# BLDC-Controller-Open-Source.net
KiCad netlist of a schematic drawn in EAGLE
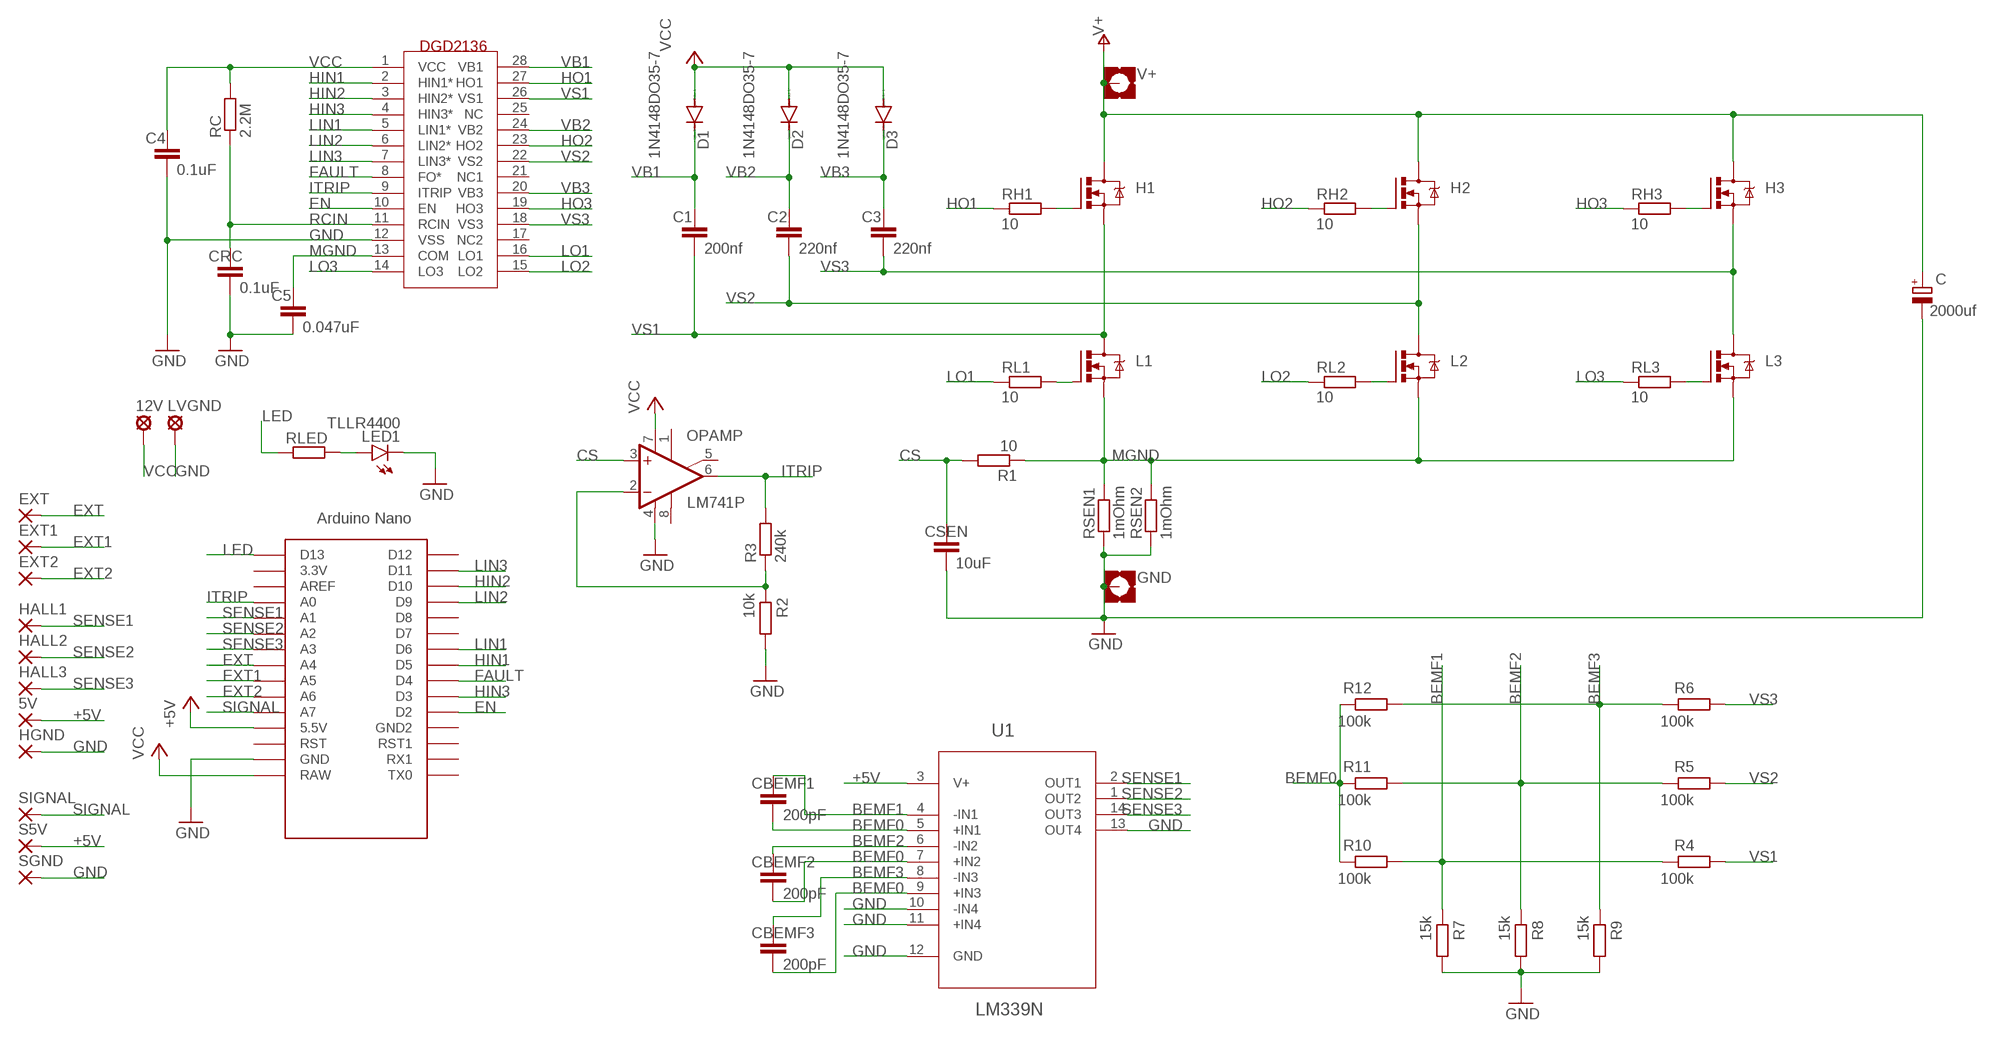
[diagram p0: schematic, sheet 1]

(export (version "E")
  (design (tool "Eeschema 10.0.6"))
  (components
    (comp (ref "5V")
      (value "1,6/0,9")
      (footprint "eagle-import:1,6_0,9")
      (libsource (lib "eagle-import") (part "1,6/0,9"))
    )
    (comp (ref "12V")
      (value "MCS10B")
      (footprint "eagle-import:MCS10B")
      (libsource (lib "eagle-import") (part "MCS10B"))
    )
    (comp (ref "C")
      (value "2000uf")
      (footprint "eagle-import:E7,5-16")
      (libsource (lib "eagle-import") (part "CPOL-EUE7.5-16"))
    )
    (comp (ref "C1")
      (value "200nf")
      (footprint "eagle-import:C025-025X050")
      (libsource (lib "eagle-import") (part "C-EU025-025X050"))
    )
    (comp (ref "C2")
      (value "220nf")
      (footprint "eagle-import:C025-025X050")
      (libsource (lib "eagle-import") (part "C-EU025-025X050"))
    )
    (comp (ref "C3")
      (value "220nf")
      (footprint "eagle-import:C025-025X050")
      (libsource (lib "eagle-import") (part "C-EU025-025X050"))
    )
    (comp (ref "C4")
      (value "0.1uF")
      (footprint "eagle-import:C025-025X050")
      (libsource (lib "eagle-import") (part "C-EU025-025X050"))
    )
    (comp (ref "C5")
      (value "0.047uF")
      (footprint "eagle-import:C025-025X050")
      (libsource (lib "eagle-import") (part "C-EU025-025X050"))
    )
    (comp (ref "CBEMF1")
      (value "200pF")
      (footprint "eagle-import:C025-025X050")
      (libsource (lib "eagle-import") (part "C-EU025-025X050"))
    )
    (comp (ref "CBEMF2")
      (value "200pF")
      (footprint "eagle-import:C025-025X050")
      (libsource (lib "eagle-import") (part "C-EU025-025X050"))
    )
    (comp (ref "CBEMF3")
      (value "200pF")
      (footprint "eagle-import:C025-025X050")
      (libsource (lib "eagle-import") (part "C-EU025-025X050"))
    )
    (comp (ref "CRC")
      (value "0.1uF")
      (footprint "eagle-import:C025-025X050")
      (libsource (lib "eagle-import") (part "C-EU025-025X050"))
    )
    (comp (ref "CSEN")
      (value "10uF")
      (footprint "eagle-import:C025-025X050")
      (libsource (lib "eagle-import") (part "C-EU025-025X050"))
    )
    (comp (ref "D1")
      (value "1N4148DO35-7")
      (footprint "eagle-import:DO35-7")
      (libsource (lib "eagle-import") (part "1N4148DO35-7"))
    )
    (comp (ref "D2")
      (value "1N4148DO35-7")
      (footprint "eagle-import:DO35-7")
      (libsource (lib "eagle-import") (part "1N4148DO35-7"))
    )
    (comp (ref "D3")
      (value "1N4148DO35-7")
      (footprint "eagle-import:DO35-7")
      (libsource (lib "eagle-import") (part "1N4148DO35-7"))
    )
    (comp (ref "EXT")
      (value "1,6/0,9")
      (footprint "eagle-import:1,6_0,9")
      (libsource (lib "eagle-import") (part "1,6/0,9"))
    )
    (comp (ref "EXT1")
      (value "1,6/0,9")
      (footprint "eagle-import:1,6_0,9")
      (libsource (lib "eagle-import") (part "1,6/0,9"))
    )
    (comp (ref "EXT2")
      (value "1,6/0,9")
      (footprint "eagle-import:1,6_0,9")
      (libsource (lib "eagle-import") (part "1,6/0,9"))
    )
    (comp (ref "GND")
      (value "MOUNT-PAD-SQUARE3.6")
      (footprint "eagle-import:3,6-PAD-SQUARE")
      (libsource (lib "eagle-import") (part "MOUNT-PAD-SQUARE3.6"))
    )
    (comp (ref "H1")
      (value "IRF540")
      (footprint "eagle-import:TO220BV")
      (libsource (lib "eagle-import") (part "IRF540"))
    )
    (comp (ref "H2")
      (value "IRF540")
      (footprint "eagle-import:TO220BV")
      (libsource (lib "eagle-import") (part "IRF540"))
    )
    (comp (ref "H3")
      (value "IRF540")
      (footprint "eagle-import:TO220BV")
      (libsource (lib "eagle-import") (part "IRF540"))
    )
    (comp (ref "HALL1")
      (value "1,6/0,9")
      (footprint "eagle-import:1,6_0,9")
      (libsource (lib "eagle-import") (part "1,6/0,9"))
    )
    (comp (ref "HALL2")
      (value "1,6/0,9")
      (footprint "eagle-import:1,6_0,9")
      (libsource (lib "eagle-import") (part "1,6/0,9"))
    )
    (comp (ref "HALL3")
      (value "1,6/0,9")
      (footprint "eagle-import:1,6_0,9")
      (libsource (lib "eagle-import") (part "1,6/0,9"))
    )
    (comp (ref "HGND")
      (value "1,6/0,9")
      (footprint "eagle-import:1,6_0,9")
      (libsource (lib "eagle-import") (part "1,6/0,9"))
    )
    (comp (ref "L1")
      (value "IRF540")
      (footprint "eagle-import:TO220BV")
      (libsource (lib "eagle-import") (part "IRF540"))
    )
    (comp (ref "L2")
      (value "IRF540")
      (footprint "eagle-import:TO220BV")
      (libsource (lib "eagle-import") (part "IRF540"))
    )
    (comp (ref "L3")
      (value "IRF540")
      (footprint "eagle-import:TO220BV")
      (libsource (lib "eagle-import") (part "IRF540"))
    )
    (comp (ref "LED1")
      (value "TLLR4400")
      (footprint "eagle-import:LED3MM")
      (fields (field (name "MF") "VISHAY SEMICONDUCTOR"))
      (libsource (lib "eagle-import") (part "TLLR4400"))
    )
    (comp (ref "LVGND")
      (value "MCS10B")
      (footprint "eagle-import:MCS10B")
      (libsource (lib "eagle-import") (part "MCS10B"))
    )
    (comp (ref "OPAMP")
      (value "LM741P")
      (footprint "eagle-import:DIL08")
      (libsource (lib "eagle-import") (part "741PLM"))
    )
    (comp (ref "R1")
      (value "10")
      (footprint "eagle-import:0204_7")
      (libsource (lib "eagle-import") (part "rcl_334_R-EU_0204/7"))
    )
    (comp (ref "R2")
      (value "10k")
      (footprint "eagle-import:0204_7")
      (libsource (lib "eagle-import") (part "rcl_334_R-EU_0204/7"))
    )
    (comp (ref "R3")
      (value "240k")
      (footprint "eagle-import:0204_7")
      (libsource (lib "eagle-import") (part "rcl_334_R-EU_0204/7"))
    )
    (comp (ref "R4")
      (value "100k")
      (footprint "eagle-import:0204_7")
      (libsource (lib "eagle-import") (part "rcl_334_R-EU_0204/7"))
    )
    (comp (ref "R5")
      (value "100k")
      (footprint "eagle-import:0204_7")
      (libsource (lib "eagle-import") (part "rcl_334_R-EU_0204/7"))
    )
    (comp (ref "R6")
      (value "100k")
      (footprint "eagle-import:0204_7")
      (libsource (lib "eagle-import") (part "rcl_334_R-EU_0204/7"))
    )
    (comp (ref "R7")
      (value "15k")
      (footprint "eagle-import:0204_7")
      (libsource (lib "eagle-import") (part "rcl_334_R-EU_0204/7"))
    )
    (comp (ref "R8")
      (value "15k")
      (footprint "eagle-import:0204_7")
      (libsource (lib "eagle-import") (part "rcl_334_R-EU_0204/7"))
    )
    (comp (ref "R9")
      (value "15k")
      (footprint "eagle-import:0204_7")
      (libsource (lib "eagle-import") (part "rcl_334_R-EU_0204/7"))
    )
    (comp (ref "R10")
      (value "100k")
      (footprint "eagle-import:0204_7")
      (libsource (lib "eagle-import") (part "rcl_334_R-EU_0204/7"))
    )
    (comp (ref "R11")
      (value "100k")
      (footprint "eagle-import:0204_7")
      (libsource (lib "eagle-import") (part "rcl_334_R-EU_0204/7"))
    )
    (comp (ref "R12")
      (value "100k")
      (footprint "eagle-import:0204_7")
      (libsource (lib "eagle-import") (part "rcl_334_R-EU_0204/7"))
    )
    (comp (ref "RC")
      (value "2.2M")
      (footprint "eagle-import:0204_7")
      (libsource (lib "eagle-import") (part "rcl_334_R-EU_0204/7"))
    )
    (comp (ref "RH1")
      (value "10")
      (footprint "eagle-import:0204_7")
      (libsource (lib "eagle-import") (part "rcl_334_R-EU_0204/7"))
    )
    (comp (ref "RH2")
      (value "10")
      (footprint "eagle-import:0204_7")
      (libsource (lib "eagle-import") (part "rcl_334_R-EU_0204/7"))
    )
    (comp (ref "RH3")
      (value "10")
      (footprint "eagle-import:0204_7")
      (libsource (lib "eagle-import") (part "rcl_334_R-EU_0204/7"))
    )
    (comp (ref "RL1")
      (value "10")
      (footprint "eagle-import:0204_7")
      (libsource (lib "eagle-import") (part "rcl_334_R-EU_0204/7"))
    )
    (comp (ref "RL2")
      (value "10")
      (footprint "eagle-import:0204_7")
      (libsource (lib "eagle-import") (part "rcl_334_R-EU_0204/7"))
    )
    (comp (ref "RL3")
      (value "10")
      (footprint "eagle-import:0204_7")
      (libsource (lib "eagle-import") (part "rcl_334_R-EU_0204/7"))
    )
    (comp (ref "RLED")
      (value "R-EU_0204/7")
      (footprint "eagle-import:0204_7")
      (libsource (lib "eagle-import") (part "rcl_334_R-EU_0204/7"))
    )
    (comp (ref "RSEN1")
      (value "1mOhm")
      (footprint "eagle-import:R2512")
      (libsource (lib "eagle-import") (part "R-EU_R2512"))
    )
    (comp (ref "RSEN2")
      (value "1mOhm")
      (footprint "eagle-import:R2512")
      (libsource (lib "eagle-import") (part "R-EU_R2512"))
    )
    (comp (ref "S5V")
      (value "1,6/0,9")
      (footprint "eagle-import:1,6_0,9")
      (libsource (lib "eagle-import") (part "1,6/0,9"))
    )
    (comp (ref "SGND")
      (value "1,6/0,9")
      (footprint "eagle-import:1,6_0,9")
      (libsource (lib "eagle-import") (part "1,6/0,9"))
    )
    (comp (ref "SIGNAL")
      (value "1,6/0,9")
      (footprint "eagle-import:1,6_0,9")
      (libsource (lib "eagle-import") (part "1,6/0,9"))
    )
    (comp (ref "U$1")
      (value "NANO")
      (footprint "eagle-import:NANO")
      (libsource (lib "eagle-import") (part "NANO"))
    )
    (comp (ref "U$2")
      (value "DGD2136")
      (footprint "eagle-import:DGD2136")
      (libsource (lib "eagle-import") (part "DGD2136"))
    )
    (comp (ref "U1")
      (value "LM339N")
      (footprint "eagle-import:DIP254P762X508-14")
      (fields (field (name "MF") "ON Semiconductor"))
      (libsource (lib "eagle-import") (part "LM339N"))
    )
    (comp (ref "V+")
      (value "MOUNT-PAD-SQUARE3.6")
      (footprint "eagle-import:3,6-PAD-SQUARE")
      (libsource (lib "eagle-import") (part "MOUNT-PAD-SQUARE3.6"))
    )
  )
  (nets
    (net (code "1") (name "+5V") (class "Default")
      (node (ref "5V") (pin "1") (pinfunction "P_1") (pintype "passive"))
      (node (ref "S5V") (pin "1") (pinfunction "P_1") (pintype "passive"))
      (node (ref "U$1") (pin "5V") (pinfunction "5.5V_5V") (pintype "bidirectional"))
      (node (ref "U1") (pin "3") (pinfunction "V+_3") (pintype "power_in"))
    )
    (net (code "2") (name "/BEMF0") (class "Default")
      (node (ref "CBEMF1") (pin "2") (pinfunction "2_2") (pintype "passive"))
      (node (ref "CBEMF2") (pin "2") (pinfunction "2_2") (pintype "passive"))
      (node (ref "CBEMF3") (pin "2") (pinfunction "2_2") (pintype "passive"))
      (node (ref "R10") (pin "2") (pinfunction "2_2") (pintype "passive"))
      (node (ref "R11") (pin "2") (pinfunction "2_2") (pintype "passive"))
      (node (ref "R12") (pin "2") (pinfunction "2_2") (pintype "passive"))
      (node (ref "U1") (pin "5") (pinfunction "+IN1_5") (pintype "input"))
      (node (ref "U1") (pin "7") (pinfunction "+IN2_7") (pintype "input"))
      (node (ref "U1") (pin "9") (pinfunction "+IN3_9") (pintype "input"))
    )
    (net (code "3") (name "/BEMF1") (class "Default")
      (node (ref "CBEMF1") (pin "1") (pinfunction "1_1") (pintype "passive"))
      (node (ref "R10") (pin "1") (pinfunction "1_1") (pintype "passive"))
      (node (ref "R4") (pin "2") (pinfunction "2_2") (pintype "passive"))
      (node (ref "R7") (pin "2") (pinfunction "2_2") (pintype "passive"))
      (node (ref "U1") (pin "4") (pinfunction "-IN1_4") (pintype "input"))
    )
    (net (code "4") (name "/BEMF2") (class "Default")
      (node (ref "CBEMF2") (pin "1") (pinfunction "1_1") (pintype "passive"))
      (node (ref "R11") (pin "1") (pinfunction "1_1") (pintype "passive"))
      (node (ref "R5") (pin "2") (pinfunction "2_2") (pintype "passive"))
      (node (ref "R8") (pin "2") (pinfunction "2_2") (pintype "passive"))
      (node (ref "U1") (pin "6") (pinfunction "-IN2_6") (pintype "input"))
    )
    (net (code "5") (name "/BEMF3") (class "Default")
      (node (ref "CBEMF3") (pin "1") (pinfunction "1_1") (pintype "passive"))
      (node (ref "R12") (pin "1") (pinfunction "1_1") (pintype "passive"))
      (node (ref "R6") (pin "2") (pinfunction "2_2") (pintype "passive"))
      (node (ref "R9") (pin "2") (pinfunction "2_2") (pintype "passive"))
      (node (ref "U1") (pin "8") (pinfunction "-IN3_8") (pintype "input"))
    )
    (net (code "6") (name "/CS") (class "Default")
      (node (ref "CSEN") (pin "1") (pinfunction "1_1") (pintype "passive"))
      (node (ref "OPAMP") (pin "3") (pinfunction "+IN_3") (pintype "input"))
      (node (ref "R1") (pin "2") (pinfunction "2_2") (pintype "passive"))
    )
    (net (code "7") (name "/EN") (class "Default")
      (node (ref "U$1") (pin "D2") (pinfunction "D2_D2") (pintype "bidirectional"))
      (node (ref "U$2") (pin "10") (pinfunction "EN_10") (pintype "bidirectional"))
    )
    (net (code "8") (name "/EXT") (class "Default")
      (node (ref "EXT") (pin "1") (pinfunction "P_1") (pintype "passive"))
      (node (ref "U$1") (pin "A4") (pinfunction "A4_A4") (pintype "bidirectional"))
    )
    (net (code "9") (name "/EXT1") (class "Default")
      (node (ref "EXT1") (pin "1") (pinfunction "P_1") (pintype "passive"))
      (node (ref "U$1") (pin "A5") (pinfunction "A5_A5") (pintype "bidirectional"))
    )
    (net (code "10") (name "/EXT2") (class "Default")
      (node (ref "EXT2") (pin "1") (pinfunction "P_1") (pintype "passive"))
      (node (ref "U$1") (pin "A6") (pinfunction "A6_A6") (pintype "bidirectional"))
    )
    (net (code "11") (name "/FAULT") (class "Default")
      (node (ref "U$1") (pin "D4") (pinfunction "D4_D4") (pintype "bidirectional"))
      (node (ref "U$2") (pin "8") (pinfunction "FO*_8") (pintype "bidirectional"))
    )
    (net (code "12") (name "/HIN1") (class "Default")
      (node (ref "U$1") (pin "D5") (pinfunction "D5_D5") (pintype "bidirectional"))
      (node (ref "U$2") (pin "2") (pinfunction "HIN1*_2") (pintype "bidirectional"))
    )
    (net (code "13") (name "/HIN2") (class "Default")
      (node (ref "U$1") (pin "D10") (pinfunction "D10_D10") (pintype "bidirectional"))
      (node (ref "U$2") (pin "3") (pinfunction "HIN2*_3") (pintype "bidirectional"))
    )
    (net (code "14") (name "/HIN3") (class "Default")
      (node (ref "U$1") (pin "D3") (pinfunction "D3_D3") (pintype "bidirectional"))
      (node (ref "U$2") (pin "4") (pinfunction "HIN3*_4") (pintype "bidirectional"))
    )
    (net (code "15") (name "/HO1") (class "Default")
      (node (ref "RH1") (pin "1") (pinfunction "1_1") (pintype "passive"))
      (node (ref "U$2") (pin "27") (pinfunction "HO1_27") (pintype "bidirectional"))
    )
    (net (code "16") (name "/HO2") (class "Default")
      (node (ref "RH2") (pin "1") (pinfunction "1_1") (pintype "passive"))
      (node (ref "U$2") (pin "23") (pinfunction "HO2_23") (pintype "bidirectional"))
    )
    (net (code "17") (name "/HO3") (class "Default")
      (node (ref "RH3") (pin "1") (pinfunction "1_1") (pintype "passive"))
      (node (ref "U$2") (pin "19") (pinfunction "HO3_19") (pintype "bidirectional"))
    )
    (net (code "18") (name "/ITRIP") (class "Default")
      (node (ref "OPAMP") (pin "6") (pinfunction "OUT_6") (pintype "output"))
      (node (ref "R3") (pin "2") (pinfunction "2_2") (pintype "passive"))
      (node (ref "U$1") (pin "A0") (pinfunction "A0_A0") (pintype "bidirectional"))
      (node (ref "U$2") (pin "9") (pinfunction "ITRIP_9") (pintype "bidirectional"))
    )
    (net (code "19") (name "/LED") (class "Default")
      (node (ref "RLED") (pin "1") (pinfunction "1_1") (pintype "passive"))
      (node (ref "U$1") (pin "D13") (pinfunction "D13_D13") (pintype "bidirectional"))
    )
    (net (code "20") (name "/LIN1") (class "Default")
      (node (ref "U$1") (pin "D6") (pinfunction "D6_D6") (pintype "bidirectional"))
      (node (ref "U$2") (pin "5") (pinfunction "LIN1*_5") (pintype "bidirectional"))
    )
    (net (code "21") (name "/LIN2") (class "Default")
      (node (ref "U$1") (pin "D9") (pinfunction "D9_D9") (pintype "bidirectional"))
      (node (ref "U$2") (pin "6") (pinfunction "LIN2*_6") (pintype "bidirectional"))
    )
    (net (code "22") (name "/LIN3") (class "Default")
      (node (ref "U$1") (pin "D11") (pinfunction "D11_D11") (pintype "bidirectional"))
      (node (ref "U$2") (pin "7") (pinfunction "LIN3*_7") (pintype "bidirectional"))
    )
    (net (code "23") (name "/LO1") (class "Default")
      (node (ref "RL1") (pin "1") (pinfunction "1_1") (pintype "passive"))
      (node (ref "U$2") (pin "16") (pinfunction "LO1_16") (pintype "bidirectional"))
    )
    (net (code "24") (name "/LO2") (class "Default")
      (node (ref "RL2") (pin "1") (pinfunction "1_1") (pintype "passive"))
      (node (ref "U$2") (pin "15") (pinfunction "LO2_15") (pintype "bidirectional"))
    )
    (net (code "25") (name "/LO3") (class "Default")
      (node (ref "RL3") (pin "1") (pinfunction "1_1") (pintype "passive"))
      (node (ref "U$2") (pin "14") (pinfunction "LO3_14") (pintype "bidirectional"))
    )
    (net (code "26") (name "/MGND") (class "Default")
      (node (ref "C5") (pin "1") (pinfunction "1_1") (pintype "passive"))
      (node (ref "L1") (pin "S") (pinfunction "S_S") (pintype "passive"))
      (node (ref "L2") (pin "S") (pinfunction "S_S") (pintype "passive"))
      (node (ref "L3") (pin "S") (pinfunction "S_S") (pintype "passive"))
      (node (ref "R1") (pin "1") (pinfunction "1_1") (pintype "passive"))
      (node (ref "RSEN1") (pin "2") (pinfunction "2_2") (pintype "passive"))
      (node (ref "RSEN2") (pin "2") (pinfunction "2_2") (pintype "passive"))
      (node (ref "U$2") (pin "13") (pinfunction "COM_13") (pintype "bidirectional"))
    )
    (net (code "27") (name "/RCIN") (class "Default")
      (node (ref "CRC") (pin "1") (pinfunction "1_1") (pintype "passive"))
      (node (ref "RC") (pin "1") (pinfunction "1_1") (pintype "passive"))
      (node (ref "U$2") (pin "11") (pinfunction "RCIN_11") (pintype "bidirectional"))
    )
    (net (code "28") (name "/SENSE1") (class "Default")
      (node (ref "HALL1") (pin "1") (pinfunction "P_1") (pintype "passive"))
      (node (ref "U$1") (pin "A1") (pinfunction "A1_A1") (pintype "bidirectional"))
      (node (ref "U1") (pin "2") (pinfunction "OUT1_2") (pintype "output"))
    )
    (net (code "29") (name "/SENSE2") (class "Default")
      (node (ref "HALL2") (pin "1") (pinfunction "P_1") (pintype "passive"))
      (node (ref "U$1") (pin "A2") (pinfunction "A2_A2") (pintype "bidirectional"))
      (node (ref "U1") (pin "1") (pinfunction "OUT2_1") (pintype "output"))
    )
    (net (code "30") (name "/SENSE3") (class "Default")
      (node (ref "HALL3") (pin "1") (pinfunction "P_1") (pintype "passive"))
      (node (ref "U$1") (pin "A3") (pinfunction "A3_A3") (pintype "bidirectional"))
      (node (ref "U1") (pin "14") (pinfunction "OUT3_14") (pintype "output"))
    )
    (net (code "31") (name "/SIGNAL") (class "Default")
      (node (ref "SIGNAL") (pin "1") (pinfunction "P_1") (pintype "passive"))
      (node (ref "U$1") (pin "A7") (pinfunction "A7_A7") (pintype "bidirectional"))
    )
    (net (code "32") (name "/VB1") (class "Default")
      (node (ref "C1") (pin "1") (pinfunction "1_1") (pintype "passive"))
      (node (ref "D1") (pin "C") (pinfunction "C_C") (pintype "passive"))
      (node (ref "U$2") (pin "28") (pinfunction "VB1_28") (pintype "bidirectional"))
    )
    (net (code "33") (name "/VB2") (class "Default")
      (node (ref "C2") (pin "1") (pinfunction "1_1") (pintype "passive"))
      (node (ref "D2") (pin "C") (pinfunction "C_C") (pintype "passive"))
      (node (ref "U$2") (pin "24") (pinfunction "VB2_24") (pintype "bidirectional"))
    )
    (net (code "34") (name "/VB3") (class "Default")
      (node (ref "C3") (pin "1") (pinfunction "1_1") (pintype "passive"))
      (node (ref "D3") (pin "C") (pinfunction "C_C") (pintype "passive"))
      (node (ref "U$2") (pin "20") (pinfunction "VB3_20") (pintype "bidirectional"))
    )
    (net (code "35") (name "/VS1") (class "Default")
      (node (ref "C1") (pin "2") (pinfunction "2_2") (pintype "passive"))
      (node (ref "H1") (pin "S") (pinfunction "S_S") (pintype "passive"))
      (node (ref "L1") (pin "D") (pinfunction "D_D") (pintype "passive"))
      (node (ref "R4") (pin "1") (pinfunction "1_1") (pintype "passive"))
      (node (ref "U$2") (pin "26") (pinfunction "VS1_26") (pintype "bidirectional"))
    )
    (net (code "36") (name "/VS2") (class "Default")
      (node (ref "C2") (pin "2") (pinfunction "2_2") (pintype "passive"))
      (node (ref "H2") (pin "S") (pinfunction "S_S") (pintype "passive"))
      (node (ref "L2") (pin "D") (pinfunction "D_D") (pintype "passive"))
      (node (ref "R5") (pin "1") (pinfunction "1_1") (pintype "passive"))
      (node (ref "U$2") (pin "22") (pinfunction "VS2_22") (pintype "bidirectional"))
    )
    (net (code "37") (name "/VS3") (class "Default")
      (node (ref "C3") (pin "2") (pinfunction "2_2") (pintype "passive"))
      (node (ref "H3") (pin "S") (pinfunction "S_S") (pintype "passive"))
      (node (ref "L3") (pin "D") (pinfunction "D_D") (pintype "passive"))
      (node (ref "R6") (pin "1") (pinfunction "1_1") (pintype "passive"))
      (node (ref "U$2") (pin "18") (pinfunction "VS3_18") (pintype "bidirectional"))
    )
    (net (code "38") (name "GND") (class "Default")
      (node (ref "C") (pin "-") (pinfunction "-_-") (pintype "passive"))
      (node (ref "C4") (pin "2") (pinfunction "2_2") (pintype "passive"))
      (node (ref "C5") (pin "2") (pinfunction "2_2") (pintype "passive"))
      (node (ref "CRC") (pin "2") (pinfunction "2_2") (pintype "passive"))
      (node (ref "CSEN") (pin "2") (pinfunction "2_2") (pintype "passive"))
      (node (ref "GND") (pin "B3,6") (pinfunction "MOUNT_B3,6") (pintype "passive"))
      (node (ref "HGND") (pin "1") (pinfunction "P_1") (pintype "passive"))
      (node (ref "LED1") (pin "K") (pinfunction "C_K") (pintype "passive"))
      (node (ref "LVGND") (pin "MP") (pinfunction "MP_MP") (pintype "passive"))
      (node (ref "OPAMP") (pin "4") (pinfunction "V-_4") (pintype "power_in"))
      (node (ref "R2") (pin "1") (pinfunction "1_1") (pintype "passive"))
      (node (ref "R7") (pin "1") (pinfunction "1_1") (pintype "passive"))
      (node (ref "R8") (pin "1") (pinfunction "1_1") (pintype "passive"))
      (node (ref "R9") (pin "1") (pinfunction "1_1") (pintype "passive"))
      (node (ref "RSEN1") (pin "1") (pinfunction "1_1") (pintype "passive"))
      (node (ref "RSEN2") (pin "1") (pinfunction "1_1") (pintype "passive"))
      (node (ref "SGND") (pin "1") (pinfunction "P_1") (pintype "passive"))
      (node (ref "U$1") (pin "GND") (pinfunction "GND_GND") (pintype "bidirectional"))
      (node (ref "U$2") (pin "12") (pinfunction "VSS_12") (pintype "bidirectional"))
      (node (ref "U1") (pin "10") (pinfunction "-IN4_10") (pintype "input"))
      (node (ref "U1") (pin "11") (pinfunction "+IN4_11") (pintype "input"))
      (node (ref "U1") (pin "12") (pinfunction "GND_12") (pintype "passive"))
      (node (ref "U1") (pin "13") (pinfunction "OUT4_13") (pintype "output"))
    )
    (net (code "39") (name "Net-(H1-PadG)") (class "Default")
      (node (ref "H1") (pin "G") (pinfunction "G_G") (pintype "passive"))
      (node (ref "RH1") (pin "2") (pinfunction "2_2") (pintype "passive"))
    )
    (net (code "40") (name "Net-(H2-PadG)") (class "Default")
      (node (ref "H2") (pin "G") (pinfunction "G_G") (pintype "passive"))
      (node (ref "RH2") (pin "2") (pinfunction "2_2") (pintype "passive"))
    )
    (net (code "41") (name "Net-(H3-PadG)") (class "Default")
      (node (ref "H3") (pin "G") (pinfunction "G_G") (pintype "passive"))
      (node (ref "RH3") (pin "2") (pinfunction "2_2") (pintype "passive"))
    )
    (net (code "42") (name "Net-(L1-PadG)") (class "Default")
      (node (ref "L1") (pin "G") (pinfunction "G_G") (pintype "passive"))
      (node (ref "RL1") (pin "2") (pinfunction "2_2") (pintype "passive"))
    )
    (net (code "43") (name "Net-(L2-PadG)") (class "Default")
      (node (ref "L2") (pin "G") (pinfunction "G_G") (pintype "passive"))
      (node (ref "RL2") (pin "2") (pinfunction "2_2") (pintype "passive"))
    )
    (net (code "44") (name "Net-(L3-PadG)") (class "Default")
      (node (ref "L3") (pin "G") (pinfunction "G_G") (pintype "passive"))
      (node (ref "RL3") (pin "2") (pinfunction "2_2") (pintype "passive"))
    )
    (net (code "45") (name "Net-(LED1-PadA)") (class "Default")
      (node (ref "LED1") (pin "A") (pinfunction "A_A") (pintype "passive"))
      (node (ref "RLED") (pin "2") (pinfunction "2_2") (pintype "passive"))
    )
    (net (code "46") (name "Net-(OPAMP--IN)") (class "Default")
      (node (ref "OPAMP") (pin "2") (pinfunction "-IN_2") (pintype "input"))
      (node (ref "R2") (pin "2") (pinfunction "2_2") (pintype "passive"))
      (node (ref "R3") (pin "1") (pinfunction "1_1") (pintype "passive"))
    )
    (net (code "47") (name "V+") (class "Default")
      (node (ref "C") (pin "+") (pinfunction "+_+") (pintype "passive"))
      (node (ref "H1") (pin "D") (pinfunction "D_D") (pintype "passive"))
      (node (ref "H2") (pin "D") (pinfunction "D_D") (pintype "passive"))
      (node (ref "H3") (pin "D") (pinfunction "D_D") (pintype "passive"))
      (node (ref "V+") (pin "B3,6") (pinfunction "MOUNT_B3,6") (pintype "passive"))
    )
    (net (code "48") (name "VCC") (class "Default")
      (node (ref "12V") (pin "MP") (pinfunction "MP_MP") (pintype "passive"))
      (node (ref "C4") (pin "1") (pinfunction "1_1") (pintype "passive"))
      (node (ref "D1") (pin "A") (pinfunction "A_A") (pintype "passive"))
      (node (ref "D2") (pin "A") (pinfunction "A_A") (pintype "passive"))
      (node (ref "D3") (pin "A") (pinfunction "A_A") (pintype "passive"))
      (node (ref "OPAMP") (pin "7") (pinfunction "V+_7") (pintype "power_in"))
      (node (ref "RC") (pin "2") (pinfunction "2_2") (pintype "passive"))
      (node (ref "U$1") (pin "RAW") (pinfunction "RAW_RAW") (pintype "bidirectional"))
      (node (ref "U$2") (pin "1") (pinfunction "VCC_1") (pintype "bidirectional"))
    )
    (net (code "49") (name "unconnected-(OPAMP-ON1-Pad1)") (class "Default")
      (node (ref "OPAMP") (pin "1") (pinfunction "ON1_1") (pintype "passive"))
    )
    (net (code "50") (name "unconnected-(OPAMP-ON2-Pad5)") (class "Default")
      (node (ref "OPAMP") (pin "5") (pinfunction "ON2_5") (pintype "passive"))
    )
    (net (code "51") (name "unconnected-(OPAMP-OPT-Pad8)") (class "Default")
      (node (ref "OPAMP") (pin "8") (pinfunction "OPT_8") (pintype "passive"))
    )
    (net (code "52") (name "unconnected-(U$1-GND2-PadGND1)") (class "Default")
      (node (ref "U$1") (pin "GND1") (pinfunction "GND2_GND1") (pintype "bidirectional"))
    )
    (net (code "53") (name "unconnected-(U$1-Pad3.3V)") (class "Default")
      (node (ref "U$1") (pin "3.3V") (pinfunction "3.3V_3.3V") (pintype "bidirectional"))
    )
    (net (code "54") (name "unconnected-(U$1-PadAREF)") (class "Default")
      (node (ref "U$1") (pin "AREF") (pinfunction "AREF_AREF") (pintype "bidirectional"))
    )
    (net (code "55") (name "unconnected-(U$1-PadD7)") (class "Default")
      (node (ref "U$1") (pin "D7") (pinfunction "D7_D7") (pintype "bidirectional"))
    )
    (net (code "56") (name "unconnected-(U$1-PadD8)") (class "Default")
      (node (ref "U$1") (pin "D8") (pinfunction "D8_D8") (pintype "bidirectional"))
    )
    (net (code "57") (name "unconnected-(U$1-PadD12)") (class "Default")
      (node (ref "U$1") (pin "D12") (pinfunction "D12_D12") (pintype "bidirectional"))
    )
    (net (code "58") (name "unconnected-(U$1-PadRST)") (class "Default")
      (node (ref "U$1") (pin "RST") (pinfunction "RST_RST") (pintype "bidirectional"))
    )
    (net (code "59") (name "unconnected-(U$1-PadRST1)") (class "Default")
      (node (ref "U$1") (pin "RST1") (pinfunction "RST1_RST1") (pintype "bidirectional"))
    )
    (net (code "60") (name "unconnected-(U$1-PadRX1)") (class "Default")
      (node (ref "U$1") (pin "RX1") (pinfunction "RX1_RX1") (pintype "bidirectional"))
    )
    (net (code "61") (name "unconnected-(U$1-PadTX0)") (class "Default")
      (node (ref "U$1") (pin "TX0") (pinfunction "TX0_TX0") (pintype "bidirectional"))
    )
    (net (code "62") (name "unconnected-(U$2-NC-Pad25)") (class "Default")
      (node (ref "U$2") (pin "25") (pinfunction "NC_25") (pintype "bidirectional"))
    )
    (net (code "63") (name "unconnected-(U$2-NC1-Pad21)") (class "Default")
      (node (ref "U$2") (pin "21") (pinfunction "NC1_21") (pintype "bidirectional"))
    )
    (net (code "64") (name "unconnected-(U$2-NC2-Pad17)") (class "Default")
      (node (ref "U$2") (pin "17") (pinfunction "NC2_17") (pintype "bidirectional"))
    )
  )
)
